# 3V3_Buck_Regulator.net
KiCad netlist of a schematic drawn in Altium Designer
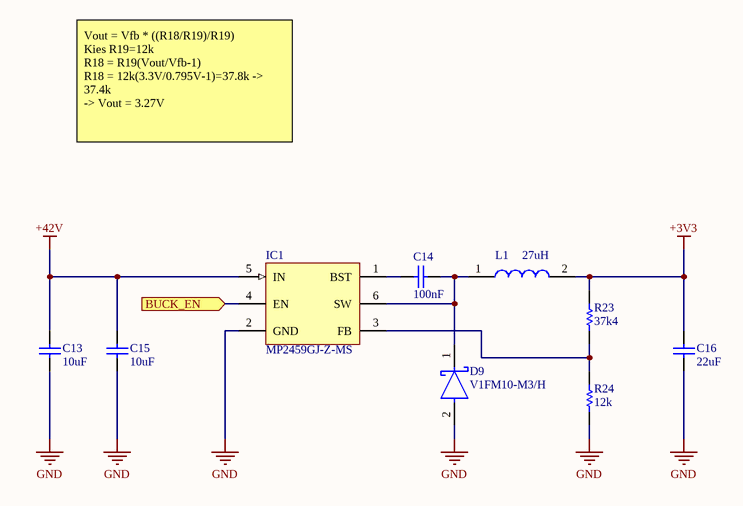
[diagram p0: 3V3_Buck_Regulator.SchDoc]

(export (version "E")
  (design (tool "Eeschema 10.0.6"))
  (components
    (comp (ref "C13")
      (value "10uF")
      (footprint "Wurth 0805 capacitor")
      (fields (field (name "Comment") "Generic Capacitor 10uF 0805"))
      (libsource (lib "Passives") (part "Generic Capacitor 10uF 0805"))
    )
    (comp (ref "C14")
      (value "100nF")
      (footprint "Wurth 0603 capacitor")
      (fields (field (name "Comment") "Generic Capacitor 100nF 0603"))
      (libsource (lib "Passives") (part "Generic Capacitor 100nF 0603"))
    )
    (comp (ref "C15")
      (value "10uF")
      (footprint "Wurth 0805 capacitor")
      (fields (field (name "Comment") "Generic Capacitor 10uF 0805"))
      (libsource (lib "Passives") (part "Generic Capacitor 10uF 0805"))
    )
    (comp (ref "C16")
      (value "22uF")
      (footprint "Wurth 0805 capacitor")
      (fields (field (name "Comment") "Generic Capacitor 22uF 0805"))
      (libsource (lib "Passives") (part "Generic Capacitor 22uF 0805"))
    )
    (comp (ref "D9")
      (value "V1FM10-M3/H")
      (footprint "FP-V1FM10-M3-H-MFG")
      (description "1A 100V SMF TRENCH SKY RECT")
      (libsource (lib "Altium Content Vault") (part "1d6ec82d83fb6aee721767c19dac4b9"))
    )
    (comp (ref "IC1")
      (value "MP2459GJ-Z-MS")
      (footprint "Texas InstrumentsSOT95P280X110-6N")
      (description "Buck Converter 4.5V-60V 600mA")
      (libsource (lib "Buck_Converter") (part "MSKSEMI MP2459GJ-Z-MS"))
    )
    (comp (ref "L1")
      (value "27uH")
      (footprint "3L COILS 5.2X5.8MM")
      (fields (field (name "MANUFACTURER") "3L Coils") (field (name "Comment") "COILS SMTDR54-270M"))
      (libsource (lib "Passives") (part "3L COILS SMTDR54-270M inductor"))
    )
    (comp (ref "R23")
      (value "37k4")
      (footprint "Wurth 0603 Resistor")
      (fields (field (name "Comment") "Generic Resistor 37k4 0603"))
      (libsource (lib "Passives") (part "Generic Resistor 37k4 0603"))
    )
    (comp (ref "R24")
      (value "12k")
      (footprint "Wurth 0603 Resistor")
      (fields (field (name "Comment") "Generic Resistor 12k 0603"))
      (libsource (lib "Passives") (part "Generic Resistor 12k 0603"))
    )
  )
  (nets
    (net (code "1") (name "+3V3") (class "Default")
      (node (ref "C16") (pin "2") (pinfunction "2_2") (pintype "passive"))
      (node (ref "L1") (pin "2") (pinfunction "2_2") (pintype "passive"))
      (node (ref "R23") (pin "2") (pinfunction "2_2") (pintype "passive"))
    )
    (net (code "2") (name "+42V") (class "Default")
      (node (ref "C13") (pin "2") (pinfunction "2_2") (pintype "passive"))
      (node (ref "C15") (pin "2") (pinfunction "2_2") (pintype "passive"))
      (node (ref "IC1") (pin "5") (pinfunction "IN_5") (pintype "input"))
    )
    (net (code "3") (name "/BUCK_EN") (class "Default")
      (node (ref "IC1") (pin "4") (pinfunction "EN_4") (pintype "passive"))
    )
    (net (code "4") (name "GND") (class "Default")
      (node (ref "C13") (pin "1") (pinfunction "1_1") (pintype "passive"))
      (node (ref "C15") (pin "1") (pinfunction "1_1") (pintype "passive"))
      (node (ref "C16") (pin "1") (pinfunction "1_1") (pintype "passive"))
      (node (ref "D9") (pin "2") (pinfunction "A_2") (pintype "passive"))
      (node (ref "IC1") (pin "2") (pinfunction "GND_2") (pintype "power_in"))
      (node (ref "R24") (pin "1") (pinfunction "1_1") (pintype "passive"))
    )
    (net (code "5") (name "Net-(D9-C)") (class "Default")
      (node (ref "C14") (pin "2") (pinfunction "2_2") (pintype "passive"))
      (node (ref "D9") (pin "1") (pinfunction "C_1") (pintype "passive"))
      (node (ref "IC1") (pin "6") (pinfunction "SW_6") (pintype "passive"))
      (node (ref "L1") (pin "1") (pinfunction "1_1") (pintype "passive"))
    )
    (net (code "6") (name "Net-(IC1-BST)") (class "Default")
      (node (ref "C14") (pin "1") (pinfunction "1_1") (pintype "passive"))
      (node (ref "IC1") (pin "1") (pinfunction "BST_1") (pintype "passive"))
    )
    (net (code "7") (name "Net-(IC1-FB)") (class "Default")
      (node (ref "IC1") (pin "3") (pinfunction "FB_3") (pintype "passive"))
      (node (ref "R23") (pin "1") (pinfunction "1_1") (pintype "passive"))
      (node (ref "R24") (pin "2") (pinfunction "2_2") (pintype "passive"))
    )
  )
)
